# BQ25756_Data_Config.net
KiCad netlist of a schematic drawn in Altium Designer
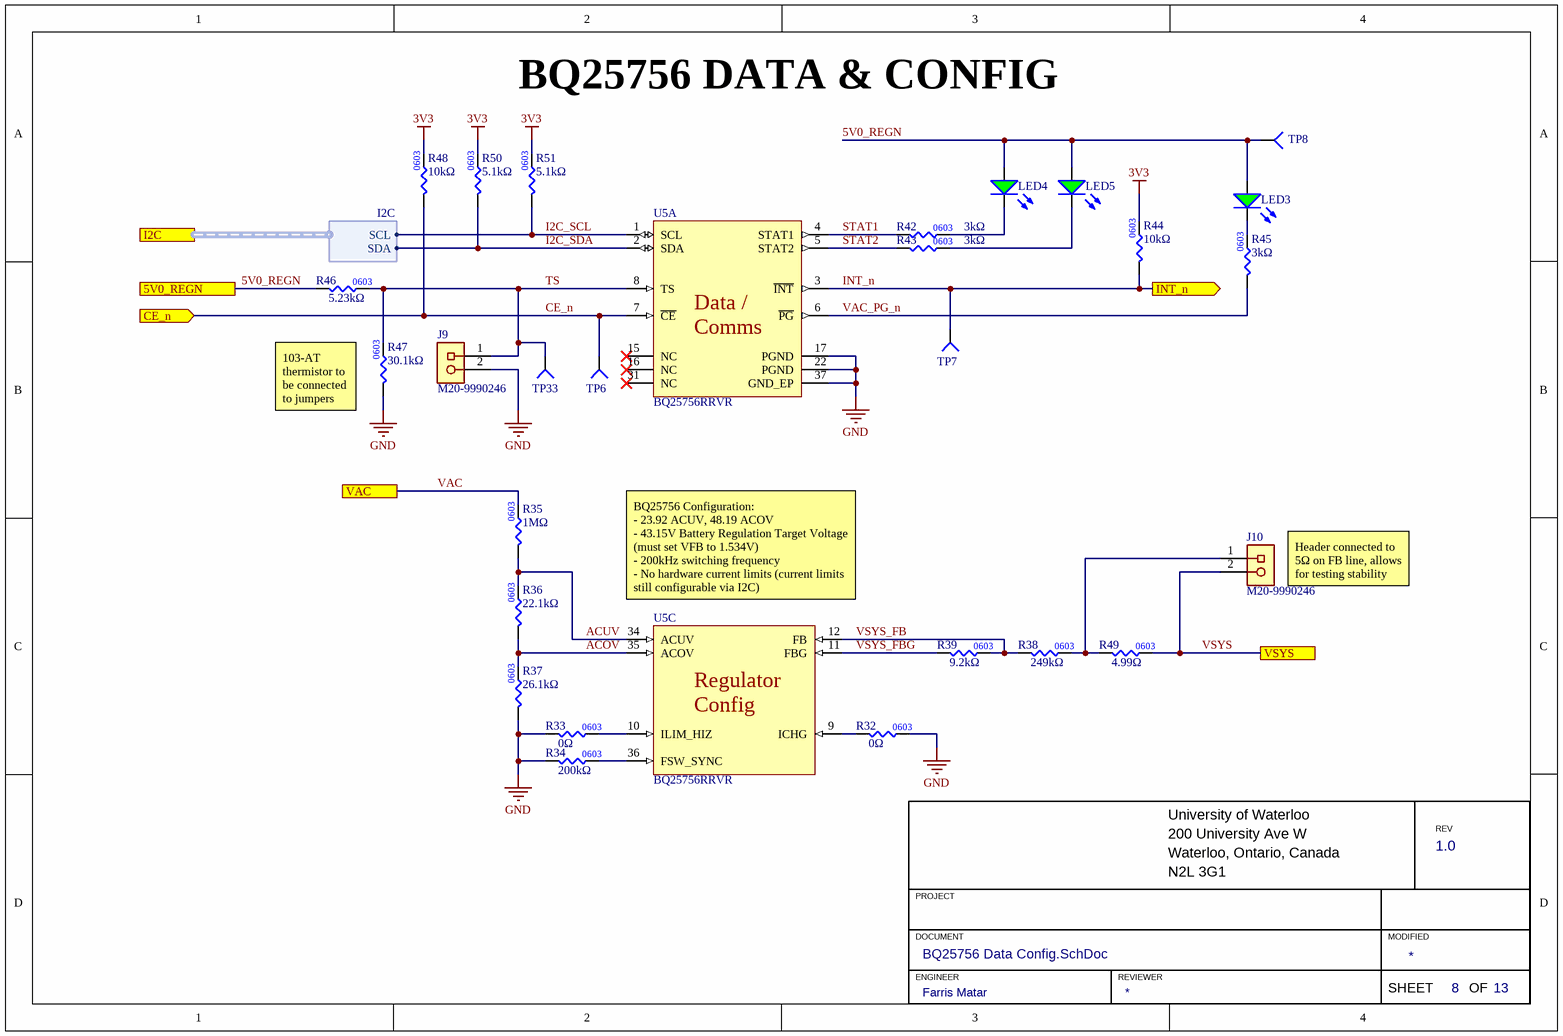
[diagram p0: BQ25756 Data Config.SchDoc]

(export (version "E")
  (design (tool "Eeschema 10.0.6"))
  (components
    (comp (ref "J9")
      (value "HEADER 2x1")
      (footprint "HDR1X2")
      (description "HEADER 2X1")
      (fields (field (name "MANUFACTURER PART NUMBER 1") "M20-9990246"))
      (libsource (lib "") (part "HEADER 2x1_1"))
    )
    (comp (ref "J10")
      (value "HEADER 2x1")
      (footprint "HDR1X2")
      (description "HEADER 2X1")
      (fields (field (name "MANUFACTURER PART NUMBER 1") "M20-9990246"))
      (libsource (lib "Personal_Schematic_Library_2022") (part "HEADER 2x1"))
    )
    (comp (ref "LED3")
      (value "LED_GREEN_0805")
      (footprint "LED_0805_GREEN")
      (description "LED GREEN DIFFUSED 0805 SMD")
      (libsource (lib "Personal_Schematic_Library_2022") (part "LED_GREEN_0805"))
    )
    (comp (ref "LED4")
      (value "LED_GREEN_0805")
      (footprint "LED_0805_GREEN")
      (description "LED GREEN DIFFUSED 0805 SMD")
      (libsource (lib "Personal_Schematic_Library_2022") (part "LED_GREEN_0805"))
    )
    (comp (ref "LED5")
      (value "LED_GREEN_0805")
      (footprint "LED_0805_GREEN")
      (description "LED GREEN DIFFUSED 0805 SMD")
      (libsource (lib "Personal_Schematic_Library_2022") (part "LED_GREEN_0805"))
    )
    (comp (ref "R32")
      (value "0Ω")
      (footprint "RES0603")
      (description "RES 0 OHM JUMPER 1/10W 0603")
      (fields (field (name "Comment") "RES_0Ω_0603"))
      (libsource (lib "Personal_Schematic_Library_2022") (part "RES_0Ω_0603"))
    )
    (comp (ref "R33")
      (value "0Ω")
      (footprint "RES0603")
      (description "RES 0 OHM JUMPER 1/10W 0603")
      (fields (field (name "Comment") "RES_0Ω_0603"))
      (libsource (lib "Personal_Schematic_Library_2022") (part "RES_0Ω_0603"))
    )
    (comp (ref "R34")
      (value "200kΩ")
      (footprint "RES0603")
      (description "RES 200K OHM 1% 1/10W 0603")
      (fields (field (name "Comment") "RES_200kΩ_0603_1%"))
      (libsource (lib "Personal_Schematic_Library_2022") (part "RES_200kΩ_0603_1%"))
    )
    (comp (ref "R35")
      (value "1MΩ")
      (footprint "RES0603")
      (description "RES 1M OHM 1% 1/10W 0603")
      (fields (field (name "Comment") "RES_1MΩ_0603_1%"))
      (libsource (lib "Personal_Schematic_Library_2022") (part "RES_1MΩ_0603_1%"))
    )
    (comp (ref "R36")
      (value "22.1kΩ")
      (footprint "RES0603")
      (description "RES 22.1K OHM 1% 1/10W 0603")
      (fields (field (name "Comment") "RES_22.1kΩ_0603_1%"))
      (libsource (lib "Personal_Schematic_Library_2022") (part "RES_22.1kΩ_0603_1%"))
    )
    (comp (ref "R37")
      (value "26.1kΩ")
      (footprint "RES0603")
      (description "RES 26.1K OHM 1% 1/10W 0603")
      (fields (field (name "Comment") "RES_26.1kΩ_0603_1%"))
      (libsource (lib "Personal_Schematic_Library_2022") (part "RES_26.1kΩ_0603_1%"))
    )
    (comp (ref "R38")
      (value "249kΩ")
      (footprint "RES0603")
      (description "RES 249K OHM 1% 1/10W 0603")
      (fields (field (name "Comment") "RES_249kΩ_0603_1%"))
      (libsource (lib "Personal_Schematic_Library_2022") (part "RES_249kΩ_0603_1%"))
    )
    (comp (ref "R39")
      (value "9.2kΩ")
      (footprint "RES0603")
      (description "RES 9.2K OHM 0.1% 1/10W 0603")
      (fields (field (name "Comment") "RES_9.2kΩ_0603_0.1%"))
      (libsource (lib "Personal_Schematic_Library_2022") (part "RES_9.2kΩ_0603_0.1%"))
    )
    (comp (ref "R42")
      (value "3kΩ")
      (footprint "RES0603")
      (description "RES 3K OHM 1% 1/10W 0603")
      (fields (field (name "Comment") "RES_3kΩ_0603_1%"))
      (libsource (lib "Personal_Schematic_Library_2022") (part "RES_3kΩ_0603_1%"))
    )
    (comp (ref "R43")
      (value "3kΩ")
      (footprint "RES0603")
      (description "RES 3K OHM 1% 1/10W 0603")
      (fields (field (name "Comment") "RES_3kΩ_0603_1%"))
      (libsource (lib "Personal_Schematic_Library_2022") (part "RES_3kΩ_0603_1%"))
    )
    (comp (ref "R44")
      (value "10kΩ")
      (footprint "RES0603")
      (description "RES 10K OHM 1% 1/8W 0603")
      (fields (field (name "Comment") "RES_10kΩ_0603_1%"))
      (libsource (lib "Personal_Schematic_Library_2022") (part "RES_10kΩ_0603_1%"))
    )
    (comp (ref "R45")
      (value "3kΩ")
      (footprint "RES0603")
      (description "RES 3K OHM 1% 1/10W 0603")
      (fields (field (name "Comment") "RES_3kΩ_0603_1%"))
      (libsource (lib "Personal_Schematic_Library_2022") (part "RES_3kΩ_0603_1%"))
    )
    (comp (ref "R46")
      (value "5.23kΩ")
      (footprint "RES0603")
      (description "RES SMD 5.23KOHM 0.1% 1/10W 0603")
      (fields (field (name "Comment") "RES_5.23kΩ_0603_0.1%"))
      (libsource (lib "Personal_Schematic_Library_2022") (part "RES_5.23kΩ_0603_0.1%"))
    )
    (comp (ref "R47")
      (value "30.1kΩ")
      (footprint "RES0603")
      (description "RES SMD 30.1KOHM 0.1% 1/10W 0603")
      (fields (field (name "Comment") "RES_30.1kΩ_0603_0.1%"))
      (libsource (lib "Personal_Schematic_Library_2022") (part "RES_30.1kΩ_0603_0.1%"))
    )
    (comp (ref "R48")
      (value "10kΩ")
      (footprint "RES0603")
      (description "RES 10K OHM 1% 1/8W 0603")
      (fields (field (name "Comment") "RES_10kΩ_0603_1%"))
      (libsource (lib "Personal_Schematic_Library_2022") (part "RES_10kΩ_0603_1%"))
    )
    (comp (ref "R49")
      (value "4.99Ω")
      (footprint "RES0603")
      (description "RES 4.99 OHM 1% 1/10W 0603")
      (fields (field (name "Comment") "RES_4.99Ω_0603_1%"))
      (libsource (lib "Personal_Schematic_Library_2022") (part "RES_4.99Ω_0603_1%"))
    )
    (comp (ref "R50")
      (value "5.1kΩ")
      (footprint "RES0603")
      (description "RES 5.1K OHM 1% 1/10W 0603")
      (fields (field (name "Comment") "RES_5.1kΩ_0603_1%"))
      (libsource (lib "Personal_Schematic_Library_2022") (part "RES_5.1kΩ_0603_1%"))
    )
    (comp (ref "R51")
      (value "5.1kΩ")
      (footprint "RES0603")
      (description "RES 5.1K OHM 1% 1/10W 0603")
      (fields (field (name "Comment") "RES_5.1kΩ_0603_1%"))
      (libsource (lib "Personal_Schematic_Library_2022") (part "RES_5.1kΩ_0603_1%"))
    )
    (comp (ref "TP6")
      (value "TESTPOINT_1MM_CIRCLE")
      (footprint "TESTPOINT_CIRCLE_1MM")
      (description "TESTPOINT 1MM CIRCLE")
      (libsource (lib "Personal_Schematic_Library_2022") (part "TESTPOINT_1MM_CIRCLE"))
    )
    (comp (ref "TP7")
      (value "TESTPOINT_1MM_CIRCLE")
      (footprint "TESTPOINT_CIRCLE_1MM")
      (description "TESTPOINT 1MM CIRCLE")
      (libsource (lib "Personal_Schematic_Library_2022") (part "TESTPOINT_1MM_CIRCLE"))
    )
    (comp (ref "TP8")
      (value "TESTPOINT_1MM_SQUARE")
      (footprint "TESTPOINT_SQUARE_1MM")
      (description "TESTPOINT 1MM SQUARE")
      (libsource (lib "Personal_Schematic_Library_2022") (part "TESTPOINT_1MM_SQUARE"))
    )
    (comp (ref "TP33")
      (value "TESTPOINT_1MM_CIRCLE")
      (footprint "TESTPOINT_CIRCLE_1MM")
      (description "TESTPOINT 1MM CIRCLE")
      (libsource (lib "Personal_Schematic_Library_2022") (part "TESTPOINT_1MM_CIRCLE"))
    )
    (comp (ref "U5")
      (value "BQ25756RRVR")
      (footprint "TI_36-VQFN")
      (description "IC BATT CHARGER BUCK-BOOST CTRLR")
      (libsource (lib "Personal_Schematic_Library_2022") (part "BQ25756RRVR"))
    )
  )
  (nets
    (net (code "2") (name "/5V0_REGN") (class "Default")
      (node (ref "LED3") (pin "1") (pinfunction "A_1") (pintype "passive"))
      (node (ref "LED4") (pin "1") (pinfunction "A_1") (pintype "passive"))
      (node (ref "LED5") (pin "1") (pinfunction "A_1") (pintype "passive"))
      (node (ref "R46") (pin "1") (pinfunction "1_1") (pintype "passive"))
      (node (ref "TP8") (pin "1") (pinfunction "=value_1") (pintype "passive"))
    )
    (net (code "3") (name "/ACOV") (class "Default")
      (node (ref "R36") (pin "1") (pinfunction "1_1") (pintype "passive"))
      (node (ref "R37") (pin "2") (pinfunction "2_2") (pintype "passive"))
      (node (ref "U5") (pin "35") (pinfunction "ACOV_35") (pintype "input"))
    )
    (net (code "4") (name "/ACUV") (class "Default")
      (node (ref "R35") (pin "1") (pinfunction "1_1") (pintype "passive"))
      (node (ref "R36") (pin "2") (pinfunction "2_2") (pintype "passive"))
      (node (ref "U5") (pin "34") (pinfunction "ACUV_34") (pintype "input"))
    )
    (net (code "5") (name "/CE_n") (class "Default")
      (node (ref "R48") (pin "1") (pinfunction "1_1") (pintype "passive"))
      (node (ref "TP6") (pin "1") (pinfunction "=value_1") (pintype "passive"))
      (node (ref "U5") (pin "7") (pinfunction "~{CE}_7") (pintype "input"))
    )
    (net (code "6") (name "/I2C_SCL") (class "Default")
      (node (ref "R51") (pin "1") (pinfunction "1_1") (pintype "passive"))
      (node (ref "U5") (pin "1") (pinfunction "SCL_1") (pintype "bidirectional"))
    )
    (net (code "7") (name "/I2C_SDA") (class "Default")
      (node (ref "R50") (pin "1") (pinfunction "1_1") (pintype "passive"))
      (node (ref "U5") (pin "2") (pinfunction "SDA_2") (pintype "bidirectional"))
    )
    (net (code "8") (name "/INT_n") (class "Default")
      (node (ref "R44") (pin "1") (pinfunction "1_1") (pintype "passive"))
      (node (ref "TP7") (pin "1") (pinfunction "=value_1") (pintype "passive"))
      (node (ref "U5") (pin "3") (pinfunction "~{INT}_3") (pintype "output"))
    )
    (net (code "9") (name "/STAT1") (class "Default")
      (node (ref "R42") (pin "1") (pinfunction "1_1") (pintype "passive"))
      (node (ref "U5") (pin "4") (pinfunction "STAT1_4") (pintype "output"))
    )
    (net (code "10") (name "/STAT2") (class "Default")
      (node (ref "R43") (pin "1") (pinfunction "1_1") (pintype "passive"))
      (node (ref "U5") (pin "5") (pinfunction "STAT2_5") (pintype "output"))
    )
    (net (code "11") (name "/TS") (class "Default")
      (node (ref "J9") (pin "1") (pinfunction "VCC_1") (pintype "passive"))
      (node (ref "R46") (pin "2") (pinfunction "2_2") (pintype "passive"))
      (node (ref "R47") (pin "2") (pinfunction "2_2") (pintype "passive"))
      (node (ref "TP33") (pin "1") (pinfunction "=value_1") (pintype "passive"))
      (node (ref "U5") (pin "8") (pinfunction "TS_8") (pintype "input"))
    )
    (net (code "12") (name "/VAC") (class "Default")
      (node (ref "R35") (pin "2") (pinfunction "2_2") (pintype "passive"))
    )
    (net (code "13") (name "/VAC_PG_n") (class "Default")
      (node (ref "R45") (pin "1") (pinfunction "1_1") (pintype "passive"))
      (node (ref "U5") (pin "6") (pinfunction "~{PG}_6") (pintype "output"))
    )
    (net (code "14") (name "/VSYS") (class "Default")
      (node (ref "J10") (pin "2") (pinfunction "2_2") (pintype "passive"))
      (node (ref "R49") (pin "2") (pinfunction "2_2") (pintype "passive"))
    )
    (net (code "15") (name "/VSYS_FB") (class "Default")
      (node (ref "R38") (pin "1") (pinfunction "1_1") (pintype "passive"))
      (node (ref "R39") (pin "2") (pinfunction "2_2") (pintype "passive"))
      (node (ref "U5") (pin "12") (pinfunction "FB_12") (pintype "input"))
    )
    (net (code "16") (name "/VSYS_FBG") (class "Default")
      (node (ref "R39") (pin "1") (pinfunction "1_1") (pintype "passive"))
      (node (ref "U5") (pin "11") (pinfunction "FBG_11") (pintype "input"))
    )
    (net (code "18") (name "3V3") (class "Default")
      (node (ref "R44") (pin "2") (pinfunction "2_2") (pintype "passive"))
      (node (ref "R48") (pin "2") (pinfunction "2_2") (pintype "passive"))
      (node (ref "R50") (pin "2") (pinfunction "2_2") (pintype "passive"))
      (node (ref "R51") (pin "2") (pinfunction "2_2") (pintype "passive"))
    )
    (net (code "19") (name "GND") (class "Default")
      (node (ref "J9") (pin "2") (pinfunction "2_2") (pintype "passive"))
      (node (ref "R32") (pin "2") (pinfunction "2_2") (pintype "passive"))
      (node (ref "R33") (pin "1") (pinfunction "1_1") (pintype "passive"))
      (node (ref "R34") (pin "1") (pinfunction "1_1") (pintype "passive"))
      (node (ref "R37") (pin "1") (pinfunction "1_1") (pintype "passive"))
      (node (ref "R47") (pin "1") (pinfunction "1_1") (pintype "passive"))
      (node (ref "U5") (pin "17") (pinfunction "PGND_17") (pintype "power_in"))
      (node (ref "U5") (pin "22") (pinfunction "PGND_22") (pintype "power_in"))
      (node (ref "U5") (pin "37") (pinfunction "GND_EP_37") (pintype "power_in"))
    )
    (net (code "20") (name "Net-(J10-VCC)") (class "Default")
      (node (ref "J10") (pin "1") (pinfunction "VCC_1") (pintype "passive"))
      (node (ref "R38") (pin "2") (pinfunction "2_2") (pintype "passive"))
      (node (ref "R49") (pin "1") (pinfunction "1_1") (pintype "passive"))
    )
    (net (code "21") (name "Net-(LED3-K)") (class "Default")
      (node (ref "LED3") (pin "2") (pinfunction "K_2") (pintype "passive"))
      (node (ref "R45") (pin "2") (pinfunction "2_2") (pintype "passive"))
    )
    (net (code "22") (name "Net-(LED4-K)") (class "Default")
      (node (ref "LED4") (pin "2") (pinfunction "K_2") (pintype "passive"))
      (node (ref "R42") (pin "2") (pinfunction "2_2") (pintype "passive"))
    )
    (net (code "23") (name "Net-(LED5-K)") (class "Default")
      (node (ref "LED5") (pin "2") (pinfunction "K_2") (pintype "passive"))
      (node (ref "R43") (pin "2") (pinfunction "2_2") (pintype "passive"))
    )
    (net (code "24") (name "Net-(U5C-FSW_SYNC)") (class "Default")
      (node (ref "R34") (pin "2") (pinfunction "2_2") (pintype "passive"))
      (node (ref "U5") (pin "36") (pinfunction "FSW_SYNC_36") (pintype "input"))
    )
    (net (code "25") (name "Net-(U5C-ICHG)") (class "Default")
      (node (ref "R32") (pin "1") (pinfunction "1_1") (pintype "passive"))
      (node (ref "U5") (pin "9") (pinfunction "ICHG_9") (pintype "input"))
    )
    (net (code "26") (name "Net-(U5C-ILIM_HIZ)") (class "Default")
      (node (ref "R33") (pin "2") (pinfunction "2_2") (pintype "passive"))
      (node (ref "U5") (pin "10") (pinfunction "ILIM_HIZ_10") (pintype "input"))
    )
    (net (code "27") (name "unconnected-(U5A-NC-Pad15)") (class "Default")
      (node (ref "U5") (pin "15") (pinfunction "NC_15") (pintype "passive+no_connect"))
    )
    (net (code "28") (name "unconnected-(U5A-NC-Pad16)") (class "Default")
      (node (ref "U5") (pin "16") (pinfunction "NC_16") (pintype "passive+no_connect"))
    )
    (net (code "29") (name "unconnected-(U5A-NC-Pad31)") (class "Default")
      (node (ref "U5") (pin "31") (pinfunction "NC_31") (pintype "passive+no_connect"))
    )
  )
)
